# AS726x-Spectral_REV-D.net
KiCad netlist of a schematic drawn in EAGLE
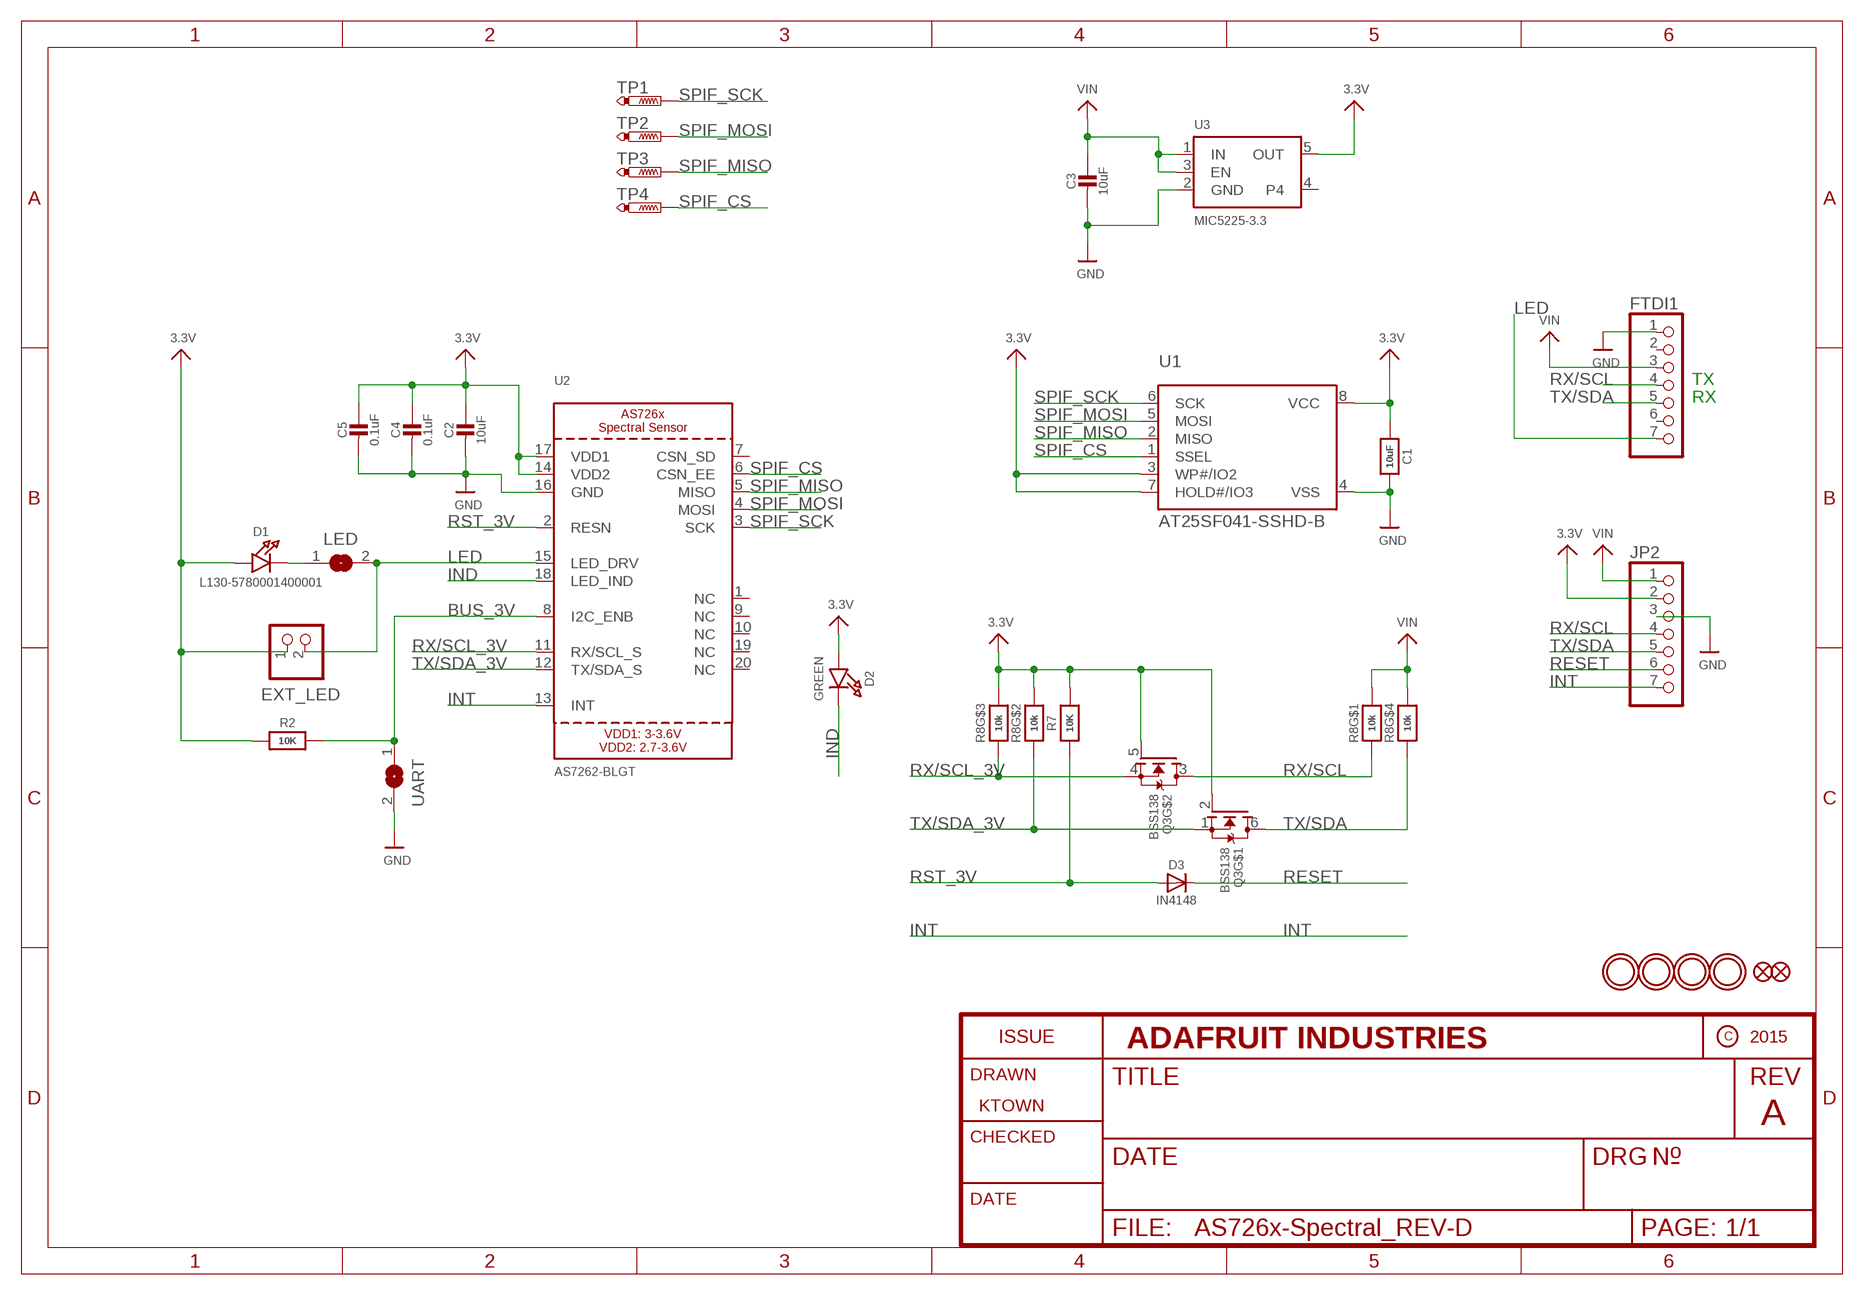
[diagram p0: schematic, sheet 1]

(export (version "E")
  (design (tool "Eeschema 10.0.6"))
  (components
    (comp (ref "C1")
      (value "10uF")
      (footprint "eagle-import:0805-NO")
      (libsource (lib "eagle-import") (part "RESISTOR0805_NOOUTLINE"))
    )
    (comp (ref "C2")
      (value "10uF")
      (footprint "eagle-import:0805-NO")
      (libsource (lib "eagle-import") (part "CAP_CERAMIC0805-NOOUTLINE"))
    )
    (comp (ref "C3")
      (value "10uF")
      (footprint "eagle-import:0805-NO")
      (libsource (lib "eagle-import") (part "CAP_CERAMIC0805-NOOUTLINE"))
    )
    (comp (ref "C4")
      (value "0.1uF")
      (footprint "eagle-import:0603-NO")
      (libsource (lib "eagle-import") (part "CAP_CERAMIC0603_NO"))
    )
    (comp (ref "C5")
      (value "0.1uF")
      (footprint "eagle-import:0603-NO")
      (libsource (lib "eagle-import") (part "CAP_CERAMIC0603_NO"))
    )
    (comp (ref "D1")
      (value "L130-5780001400001")
      (footprint "eagle-import:EVERLIGHT_45-21")
      (libsource (lib "eagle-import") (part "LEDEV45-21"))
    )
    (comp (ref "D2")
      (value "GREEN")
      (footprint "eagle-import:CHIPLED_0805_NOOUTLINE")
      (libsource (lib "eagle-import") (part "LED0805_NOOUTLINE"))
    )
    (comp (ref "D3")
      (value "IN4148")
      (footprint "eagle-import:SOD-323")
      (libsource (lib "eagle-import") (part "DIODESOD-323"))
    )
    (comp (ref "EXT_LED")
      (value "HEADER-1X2ROUND")
      (footprint "eagle-import:1X02_ROUND")
      (libsource (lib "eagle-import") (part "HEADER-1X2ROUND"))
    )
    (comp (ref "FID2")
      (value "FIDUCIAL_1MM")
      (footprint "eagle-import:FIDUCIAL_1MM")
      (libsource (lib "eagle-import") (part "FIDUCIAL_1MM"))
    )
    (comp (ref "FID3")
      (value "FIDUCIAL_1MM")
      (footprint "eagle-import:FIDUCIAL_1MM")
      (libsource (lib "eagle-import") (part "FIDUCIAL_1MM"))
    )
    (comp (ref "FTDI1")
      (value "HEADER-1X7ROUND")
      (footprint "eagle-import:1X07_ROUND")
      (libsource (lib "eagle-import") (part "HEADER-1X7ROUND"))
    )
    (comp (ref "JP2")
      (value "HEADER-1X7ROUND")
      (footprint "eagle-import:1X07_ROUND")
      (libsource (lib "eagle-import") (part "HEADER-1X7ROUND"))
    )
    (comp (ref "LED")
      (value "SOLDERJUMPERCLOSED")
      (footprint "eagle-import:SOLDERJUMPER_CLOSEDWIRE")
      (libsource (lib "eagle-import") (part "SOLDERJUMPERCLOSED"))
    )
    (comp (ref "Q3")
      (value "BSS138")
      (footprint "eagle-import:SOT363")
      (libsource (lib "eagle-import") (part "MOSFET-N_DUAL"))
    )
    (comp (ref "R2")
      (value "10K")
      (footprint "eagle-import:0805-NO")
      (libsource (lib "eagle-import") (part "RESISTOR0805_NOOUTLINE"))
    )
    (comp (ref "R7")
      (value "10K")
      (footprint "eagle-import:0603-NO")
      (libsource (lib "eagle-import") (part "microbuilder_09_Nov_2015_RESISTOR_0603_NOOUT"))
    )
    (comp (ref "R8")
      (value "10k")
      (footprint "eagle-import:RESPACK_4X0603_NO")
      (libsource (lib "eagle-import") (part "RESISTOR_4PACK_NO"))
    )
    (comp (ref "TP1")
      (value "PTR1TP15R")
      (footprint "eagle-import:TP15R")
      (libsource (lib "eagle-import") (part "PTR1TP15R"))
    )
    (comp (ref "TP2")
      (value "PTR1TP15R")
      (footprint "eagle-import:TP15R")
      (libsource (lib "eagle-import") (part "PTR1TP15R"))
    )
    (comp (ref "TP3")
      (value "PTR1TP15R")
      (footprint "eagle-import:TP15R")
      (libsource (lib "eagle-import") (part "PTR1TP15R"))
    )
    (comp (ref "TP4")
      (value "PTR1TP15R")
      (footprint "eagle-import:TP15R")
      (libsource (lib "eagle-import") (part "PTR1TP15R"))
    )
    (comp (ref "U$2")
      (value "MOUNTINGHOLE2.5")
      (footprint "eagle-import:MOUNTINGHOLE_2.5_PLATED")
      (libsource (lib "eagle-import") (part "MOUNTINGHOLE2.5"))
    )
    (comp (ref "U$3")
      (value "MOUNTINGHOLE2.5")
      (footprint "eagle-import:MOUNTINGHOLE_2.5_PLATED")
      (libsource (lib "eagle-import") (part "MOUNTINGHOLE2.5"))
    )
    (comp (ref "U$22")
      (value "MOUNTINGHOLE2.5")
      (footprint "eagle-import:MOUNTINGHOLE_2.5_PLATED")
      (libsource (lib "eagle-import") (part "MOUNTINGHOLE2.5"))
    )
    (comp (ref "U$23")
      (value "MOUNTINGHOLE2.5")
      (footprint "eagle-import:MOUNTINGHOLE_2.5_PLATED")
      (libsource (lib "eagle-import") (part "MOUNTINGHOLE2.5"))
    )
    (comp (ref "U1")
      (value "AT25SF041-SSHD-B")
      (footprint "eagle-import:SOIC8_150MIL")
      (libsource (lib "eagle-import") (part "SPIFLASH_SOIC8"))
    )
    (comp (ref "U2")
      (value "AS7262-BLGT")
      (footprint "eagle-import:AS726X_LGA20")
      (libsource (lib "eagle-import") (part "AS726X_SPECTRAL"))
    )
    (comp (ref "U3")
      (value "MIC5225-3.3")
      (footprint "eagle-import:SOT23-5")
      (libsource (lib "eagle-import") (part "VREG_SOT23-5"))
    )
    (comp (ref "UART")
      (value "SOLDERJUMPER")
      (footprint "eagle-import:SOLDERJUMPER_ARROW_NOPASTE")
      (libsource (lib "eagle-import") (part "SOLDERJUMPER"))
    )
  )
  (nets
    (net (code "1") (name "/BUS_3V") (class "Default")
      (node (ref "R2") (pin "2") (pinfunction "2_2") (pintype "passive"))
      (node (ref "U2") (pin "8") (pinfunction "I2C_ENB_8") (pintype "input"))
      (node (ref "UART") (pin "1") (pinfunction "1_1") (pintype "passive"))
    )
    (net (code "2") (name "/IND") (class "Default")
      (node (ref "D2") (pin "C") (pinfunction "C_C") (pintype "passive"))
      (node (ref "U2") (pin "18") (pinfunction "LED_IND_18") (pintype "bidirectional"))
    )
    (net (code "3") (name "/INT") (class "Default")
      (node (ref "JP2") (pin "7") (pinfunction "7_7") (pintype "passive"))
      (node (ref "U2") (pin "13") (pinfunction "INT_13") (pintype "output"))
    )
    (net (code "4") (name "/LED") (class "Default")
      (node (ref "EXT_LED") (pin "2") (pinfunction "2_2") (pintype "passive"))
      (node (ref "FTDI1") (pin "7") (pinfunction "7_7") (pintype "passive"))
      (node (ref "LED") (pin "2") (pinfunction "2_2") (pintype "passive"))
      (node (ref "U2") (pin "15") (pinfunction "LED_DRV_15") (pintype "bidirectional"))
    )
    (net (code "5") (name "/RESET") (class "Default")
      (node (ref "D3") (pin "C") (pinfunction "C_C") (pintype "passive"))
      (node (ref "JP2") (pin "6") (pinfunction "6_6") (pintype "passive"))
    )
    (net (code "6") (name "/RST_3V") (class "Default")
      (node (ref "D3") (pin "A") (pinfunction "A_A") (pintype "passive"))
      (node (ref "R7") (pin "1") (pinfunction "1_1") (pintype "passive"))
      (node (ref "U2") (pin "2") (pinfunction "RESN_2") (pintype "input"))
    )
    (net (code "7") (name "/RX{slash}SCL") (class "Default")
      (node (ref "FTDI1") (pin "4") (pinfunction "4_4") (pintype "passive"))
      (node (ref "JP2") (pin "4") (pinfunction "4_4") (pintype "passive"))
      (node (ref "Q3") (pin "3") (pinfunction "D_3") (pintype "bidirectional"))
      (node (ref "R8") (pin "1") (pinfunction "1_1") (pintype "passive"))
    )
    (net (code "8") (name "/RX{slash}SCL_3V") (class "Default")
      (node (ref "Q3") (pin "4") (pinfunction "S_4") (pintype "bidirectional"))
      (node (ref "R8") (pin "3") (pinfunction "1_3") (pintype "passive"))
      (node (ref "U2") (pin "11") (pinfunction "RX/SCL_S_11") (pintype "bidirectional"))
    )
    (net (code "9") (name "/SPIF_CS") (class "Default")
      (node (ref "TP4") (pin "TP") (pinfunction "TP_TP") (pintype "input"))
      (node (ref "U1") (pin "1") (pinfunction "SSEL_1") (pintype "bidirectional"))
      (node (ref "U2") (pin "6") (pinfunction "CSN_EE_6") (pintype "output"))
    )
    (net (code "10") (name "/SPIF_MISO") (class "Default")
      (node (ref "TP3") (pin "TP") (pinfunction "TP_TP") (pintype "input"))
      (node (ref "U1") (pin "2") (pinfunction "MISO_2") (pintype "bidirectional"))
      (node (ref "U2") (pin "5") (pinfunction "MISO_5") (pintype "output"))
    )
    (net (code "11") (name "/SPIF_MOSI") (class "Default")
      (node (ref "TP2") (pin "TP") (pinfunction "TP_TP") (pintype "input"))
      (node (ref "U1") (pin "5") (pinfunction "MOSI_5") (pintype "bidirectional"))
      (node (ref "U2") (pin "4") (pinfunction "MOSI_4") (pintype "input"))
    )
    (net (code "12") (name "/SPIF_SCK") (class "Default")
      (node (ref "TP1") (pin "TP") (pinfunction "TP_TP") (pintype "input"))
      (node (ref "U1") (pin "6") (pinfunction "SCK_6") (pintype "bidirectional"))
      (node (ref "U2") (pin "3") (pinfunction "SCK_3") (pintype "input"))
    )
    (net (code "13") (name "/TX{slash}SDA") (class "Default")
      (node (ref "FTDI1") (pin "5") (pinfunction "5_5") (pintype "passive"))
      (node (ref "JP2") (pin "5") (pinfunction "5_5") (pintype "passive"))
      (node (ref "Q3") (pin "6") (pinfunction "D_6") (pintype "bidirectional"))
      (node (ref "R8") (pin "4") (pinfunction "1_4") (pintype "passive"))
    )
    (net (code "14") (name "/TX{slash}SDA_3V") (class "Default")
      (node (ref "Q3") (pin "1") (pinfunction "S_1") (pintype "bidirectional"))
      (node (ref "R8") (pin "2") (pinfunction "1_2") (pintype "passive"))
      (node (ref "U2") (pin "12") (pinfunction "TX/SDA_S_12") (pintype "bidirectional"))
    )
    (net (code "15") (name "3.3V") (class "Default")
      (node (ref "C1") (pin "1") (pinfunction "1_1") (pintype "passive"))
      (node (ref "C2") (pin "1") (pinfunction "1_1") (pintype "passive"))
      (node (ref "C4") (pin "1") (pinfunction "1_1") (pintype "passive"))
      (node (ref "C5") (pin "1") (pinfunction "1_1") (pintype "passive"))
      (node (ref "D1") (pin "A") (pinfunction "A_A") (pintype "passive"))
      (node (ref "D2") (pin "A") (pinfunction "A_A") (pintype "passive"))
      (node (ref "EXT_LED") (pin "1") (pinfunction "1_1") (pintype "passive"))
      (node (ref "JP2") (pin "2") (pinfunction "2_2") (pintype "passive"))
      (node (ref "Q3") (pin "2") (pinfunction "G_2") (pintype "bidirectional"))
      (node (ref "Q3") (pin "5") (pinfunction "G_5") (pintype "bidirectional"))
      (node (ref "R2") (pin "1") (pinfunction "1_1") (pintype "passive"))
      (node (ref "R7") (pin "2") (pinfunction "2_2") (pintype "passive"))
      (node (ref "R8") (pin "6") (pinfunction "2_6") (pintype "passive"))
      (node (ref "R8") (pin "7") (pinfunction "2_7") (pintype "passive"))
      (node (ref "U1") (pin "3") (pinfunction "WP#/IO2_3") (pintype "bidirectional"))
      (node (ref "U1") (pin "7") (pinfunction "HOLD#/IO3_7") (pintype "bidirectional"))
      (node (ref "U1") (pin "8") (pinfunction "VCC_8") (pintype "bidirectional"))
      (node (ref "U2") (pin "14") (pinfunction "VDD2_14") (pintype "power_in"))
      (node (ref "U2") (pin "17") (pinfunction "VDD1_17") (pintype "power_in"))
      (node (ref "U3") (pin "5") (pinfunction "OUT_5") (pintype "power_in"))
    )
    (net (code "16") (name "GND") (class "Default")
      (node (ref "C1") (pin "2") (pinfunction "2_2") (pintype "passive"))
      (node (ref "C2") (pin "2") (pinfunction "2_2") (pintype "passive"))
      (node (ref "C3") (pin "2") (pinfunction "2_2") (pintype "passive"))
      (node (ref "C4") (pin "2") (pinfunction "2_2") (pintype "passive"))
      (node (ref "C5") (pin "2") (pinfunction "2_2") (pintype "passive"))
      (node (ref "FTDI1") (pin "1") (pinfunction "1_1") (pintype "passive"))
      (node (ref "JP2") (pin "3") (pinfunction "3_3") (pintype "passive"))
      (node (ref "U1") (pin "4") (pinfunction "VSS_4") (pintype "bidirectional"))
      (node (ref "U2") (pin "16") (pinfunction "GND_16") (pintype "power_in"))
      (node (ref "U3") (pin "2") (pinfunction "GND_2") (pintype "power_in"))
      (node (ref "UART") (pin "2") (pinfunction "2_2") (pintype "passive"))
    )
    (net (code "17") (name "Net-(D1-C)") (class "Default")
      (node (ref "D1") (pin "K") (pinfunction "C_K") (pintype "passive"))
      (node (ref "LED") (pin "1") (pinfunction "1_1") (pintype "passive"))
    )
    (net (code "18") (name "VIN") (class "Default")
      (node (ref "C3") (pin "1") (pinfunction "1_1") (pintype "passive"))
      (node (ref "FTDI1") (pin "3") (pinfunction "3_3") (pintype "passive"))
      (node (ref "JP2") (pin "1") (pinfunction "1_1") (pintype "passive"))
      (node (ref "R8") (pin "5") (pinfunction "2_5") (pintype "passive"))
      (node (ref "R8") (pin "8") (pinfunction "2_8") (pintype "passive"))
      (node (ref "U3") (pin "1") (pinfunction "IN_1") (pintype "power_in"))
      (node (ref "U3") (pin "3") (pinfunction "EN_3") (pintype "input"))
    )
    (net (code "19") (name "unconnected-(FTDI1-Pad2)") (class "Default")
      (node (ref "FTDI1") (pin "2") (pinfunction "2_2") (pintype "passive"))
    )
    (net (code "20") (name "unconnected-(FTDI1-Pad6)") (class "Default")
      (node (ref "FTDI1") (pin "6") (pinfunction "6_6") (pintype "passive"))
    )
    (net (code "21") (name "unconnected-(U2-CSN_SD-Pad7)") (class "Default")
      (node (ref "U2") (pin "7") (pinfunction "CSN_SD_7") (pintype "output"))
    )
    (net (code "22") (name "unconnected-(U2-NC-Pad1)") (class "Default")
      (node (ref "U2") (pin "1") (pinfunction "NC_1") (pintype "no_connect"))
    )
    (net (code "23") (name "unconnected-(U2-NC-Pad9)") (class "Default")
      (node (ref "U2") (pin "9") (pinfunction "NC_9") (pintype "no_connect"))
    )
    (net (code "24") (name "unconnected-(U2-NC-Pad10)") (class "Default")
      (node (ref "U2") (pin "10") (pinfunction "NC_10") (pintype "no_connect"))
    )
    (net (code "25") (name "unconnected-(U2-NC-Pad19)") (class "Default")
      (node (ref "U2") (pin "19") (pinfunction "NC_19") (pintype "no_connect"))
    )
    (net (code "26") (name "unconnected-(U2-NC-Pad20)") (class "Default")
      (node (ref "U2") (pin "20") (pinfunction "NC_20") (pintype "no_connect"))
    )
    (net (code "27") (name "unconnected-(U3-P4-Pad4)") (class "Default")
      (node (ref "U3") (pin "4") (pinfunction "P4_4") (pintype "bidirectional"))
    )
  )
)
